# MicrophoneArray.net
KiCad netlist of a schematic drawn in Altium Designer
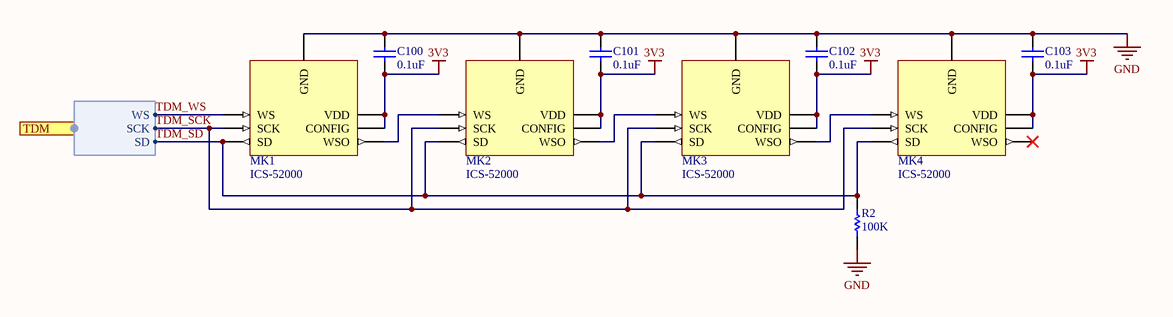
[diagram p0: MicrophoneArray.SchDoc]

(export (version "E")
  (design (tool "Eeschema 10.0.6"))
  (components
    (comp (ref "C100")
      (value "0.1uF")
      (footprint "C0402[1005X55]")
      (description "0.1uF 6.3V 10% 0402 (1005 Metric)")
      (fields (field (name "PARTNUMBER") "GRM155R70J104KA01D") (field (name "MANUFACTURER") "Murata"))
      (libsource (lib "Capacitors") (part "CAP_0.1uF_6.3V_0402_10%"))
    )
    (comp (ref "C101")
      (value "0.1uF")
      (footprint "C0402[1005X55]")
      (description "0.1uF 6.3V 10% 0402 (1005 Metric)")
      (fields (field (name "PARTNUMBER") "GRM155R70J104KA01D") (field (name "MANUFACTURER") "Murata"))
      (libsource (lib "Capacitors") (part "CAP_0.1uF_6.3V_0402_10%"))
    )
    (comp (ref "C102")
      (value "0.1uF")
      (footprint "C0402[1005X55]")
      (description "0.1uF 6.3V 10% 0402 (1005 Metric)")
      (fields (field (name "PARTNUMBER") "GRM155R70J104KA01D") (field (name "MANUFACTURER") "Murata"))
      (libsource (lib "Capacitors") (part "CAP_0.1uF_6.3V_0402_10%"))
    )
    (comp (ref "C103")
      (value "0.1uF")
      (footprint "C0402[1005X55]")
      (description "0.1uF 6.3V 10% 0402 (1005 Metric)")
      (fields (field (name "PARTNUMBER") "GRM155R70J104KA01D") (field (name "MANUFACTURER") "Murata"))
      (libsource (lib "Capacitors") (part "CAP_0.1uF_6.3V_0402_10%"))
    )
    (comp (ref "MK1")
      (value "ICS-52000")
      (footprint "MIC")
      (description "MIC MEMS DIGITAL OMNI -26DB")
      (fields (field (name "MANUFACTURER") "TDK InvenSense"))
      (libsource (lib "Components") (part "ICS-52000"))
    )
    (comp (ref "MK2")
      (value "ICS-52000")
      (footprint "MIC")
      (description "MIC MEMS DIGITAL OMNI -26DB")
      (fields (field (name "MANUFACTURER") "TDK InvenSense"))
      (libsource (lib "Components") (part "ICS-52000"))
    )
    (comp (ref "MK3")
      (value "ICS-52000")
      (footprint "MIC")
      (description "MIC MEMS DIGITAL OMNI -26DB")
      (fields (field (name "MANUFACTURER") "TDK InvenSense"))
      (libsource (lib "Components") (part "ICS-52000"))
    )
    (comp (ref "MK4")
      (value "ICS-52000")
      (footprint "MIC")
      (description "MIC MEMS DIGITAL OMNI -26DB")
      (fields (field (name "MANUFACTURER") "TDK InvenSense"))
      (libsource (lib "Components") (part "ICS-52000"))
    )
    (comp (ref "R2")
      (value "100K")
      (footprint "R0402[1005]")
      (description "100K 0.063W 1% 0402 (1005 Metric)")
      (fields (field (name "MANUFACTURER") "KOA Speer") (field (name "PARTNUMBER") "RK73H1ETTP1003F"))
      (libsource (lib "Resistors") (part "RES_100K_0402_1%"))
    )
  )
  (nets
    (net (code "2") (name "/TDM_SCK") (class "Default")
      (node (ref "MK1") (pin "6") (pinfunction "SCK_6") (pintype "input"))
      (node (ref "MK2") (pin "6") (pinfunction "SCK_6") (pintype "input"))
      (node (ref "MK3") (pin "6") (pinfunction "SCK_6") (pintype "input"))
      (node (ref "MK4") (pin "6") (pinfunction "SCK_6") (pintype "input"))
    )
    (net (code "3") (name "/TDM_SD") (class "Default")
      (node (ref "MK1") (pin "7") (pinfunction "SD_7") (pintype "output"))
      (node (ref "MK2") (pin "7") (pinfunction "SD_7") (pintype "output"))
      (node (ref "MK3") (pin "7") (pinfunction "SD_7") (pintype "output"))
      (node (ref "MK4") (pin "7") (pinfunction "SD_7") (pintype "output"))
      (node (ref "R2") (pin "2") (pinfunction "2_2") (pintype "passive"))
    )
    (net (code "4") (name "/TDM_WS") (class "Default")
      (node (ref "MK1") (pin "5") (pinfunction "WS_5") (pintype "input"))
    )
    (net (code "6") (name "3V3") (class "Default")
      (node (ref "C100") (pin "1") (pinfunction "1_1") (pintype "passive"))
      (node (ref "C101") (pin "1") (pinfunction "1_1") (pintype "passive"))
      (node (ref "C102") (pin "1") (pinfunction "1_1") (pintype "passive"))
      (node (ref "C103") (pin "1") (pinfunction "1_1") (pintype "passive"))
      (node (ref "MK1") (pin "2") (pinfunction "CONFIG_2") (pintype "passive"))
      (node (ref "MK1") (pin "3") (pinfunction "VDD_3") (pintype "power_in"))
      (node (ref "MK2") (pin "2") (pinfunction "CONFIG_2") (pintype "passive"))
      (node (ref "MK2") (pin "3") (pinfunction "VDD_3") (pintype "power_in"))
      (node (ref "MK3") (pin "2") (pinfunction "CONFIG_2") (pintype "passive"))
      (node (ref "MK3") (pin "3") (pinfunction "VDD_3") (pintype "power_in"))
      (node (ref "MK4") (pin "2") (pinfunction "CONFIG_2") (pintype "passive"))
      (node (ref "MK4") (pin "3") (pinfunction "VDD_3") (pintype "power_in"))
    )
    (net (code "7") (name "GND") (class "Default")
      (node (ref "C100") (pin "2") (pinfunction "2_2") (pintype "passive"))
      (node (ref "C101") (pin "2") (pinfunction "2_2") (pintype "passive"))
      (node (ref "C102") (pin "2") (pinfunction "2_2") (pintype "passive"))
      (node (ref "C103") (pin "2") (pinfunction "2_2") (pintype "passive"))
      (node (ref "MK1") (pin "4") (pinfunction "GND_4") (pintype "power_in"))
      (node (ref "MK2") (pin "4") (pinfunction "GND_4") (pintype "power_in"))
      (node (ref "MK3") (pin "4") (pinfunction "GND_4") (pintype "power_in"))
      (node (ref "MK4") (pin "4") (pinfunction "GND_4") (pintype "power_in"))
      (node (ref "R2") (pin "1") (pinfunction "1_1") (pintype "passive"))
    )
    (net (code "8") (name "Net-(MK1-WSO)") (class "Default")
      (node (ref "MK1") (pin "1") (pinfunction "WSO_1") (pintype "output"))
      (node (ref "MK2") (pin "5") (pinfunction "WS_5") (pintype "input"))
    )
    (net (code "9") (name "Net-(MK2-WSO)") (class "Default")
      (node (ref "MK2") (pin "1") (pinfunction "WSO_1") (pintype "output"))
      (node (ref "MK3") (pin "5") (pinfunction "WS_5") (pintype "input"))
    )
    (net (code "10") (name "Net-(MK3-WSO)") (class "Default")
      (node (ref "MK3") (pin "1") (pinfunction "WSO_1") (pintype "output"))
      (node (ref "MK4") (pin "5") (pinfunction "WS_5") (pintype "input"))
    )
    (net (code "11") (name "unconnected-(MK4-WSO-Pad1)") (class "Default")
      (node (ref "MK4") (pin "1") (pinfunction "WSO_1") (pintype "output+no_connect"))
    )
  )
)
